# LNA.net
KiCad netlist of a schematic drawn in Altium Designer
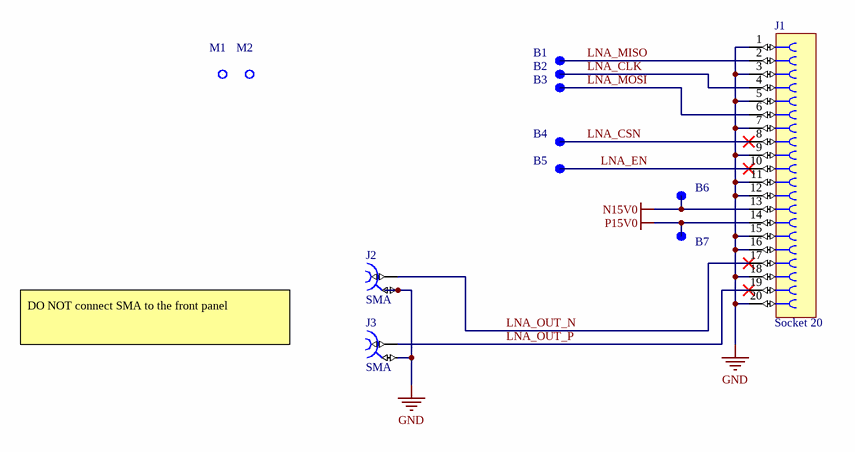
[diagram p0: LNA.SchDoc]

(export (version "E")
  (design (tool "Eeschema 10.0.6"))
  (components
    (comp (ref "B1")
      (value "SMD Pad")
      (footprint "C100")
      (description "Pad")
      (fields (field (name "PART NUMBER") "SMD_PAD_D1MM") (field (name "AUTHOR") "CERN DEM JLC"))
      (libsource (lib "Eletro-mechanical") (part "Single SMD Pad (Round)"))
    )
    (comp (ref "B2")
      (value "SMD Pad")
      (footprint "C100")
      (description "Pad")
      (fields (field (name "PART NUMBER") "SMD_PAD_D1MM") (field (name "AUTHOR") "CERN DEM JLC"))
      (libsource (lib "Eletro-mechanical") (part "Single SMD Pad (Round)"))
    )
    (comp (ref "B3")
      (value "SMD Pad")
      (footprint "C100")
      (description "Pad")
      (fields (field (name "PART NUMBER") "SMD_PAD_D1MM") (field (name "AUTHOR") "CERN DEM JLC"))
      (libsource (lib "Eletro-mechanical") (part "Single SMD Pad (Round)"))
    )
    (comp (ref "B4")
      (value "SMD Pad")
      (footprint "C100")
      (description "Pad")
      (fields (field (name "PART NUMBER") "SMD_PAD_D1MM") (field (name "AUTHOR") "CERN DEM JLC"))
      (libsource (lib "Eletro-mechanical") (part "Single SMD Pad (Round)"))
    )
    (comp (ref "B5")
      (value "SMD Pad")
      (footprint "C100")
      (description "Pad")
      (fields (field (name "PART NUMBER") "SMD_PAD_D1MM") (field (name "AUTHOR") "CERN DEM JLC"))
      (libsource (lib "Eletro-mechanical") (part "Single SMD Pad (Round)"))
    )
    (comp (ref "B6")
      (value "SMD Pad")
      (footprint "C100")
      (description "Pad")
      (fields (field (name "PART NUMBER") "SMD_PAD_D1MM") (field (name "AUTHOR") "CERN DEM JLC"))
      (libsource (lib "Eletro-mechanical") (part "Single SMD Pad (Round)"))
    )
    (comp (ref "B7")
      (value "SMD Pad")
      (footprint "C100")
      (description "Pad")
      (fields (field (name "PART NUMBER") "SMD_PAD_D1MM") (field (name "AUTHOR") "CERN DEM JLC"))
      (libsource (lib "Eletro-mechanical") (part "Single SMD Pad (Round)"))
    )
    (comp (ref "J1")
      (value "Socket 20")
      (footprint "SAMTEC_SSW-110-01-G-D")
      (description "Connector 20 Female")
      (fields
        (field (name "PART NUMBER") "SAMTEC_SSW-110-01-G-D")
        (field (name "MANUFACTURER") "SAMTEC")
        (field (name "AUTHOR") "CERN DEM JLC")
      )
      (libsource (lib "Connectors") (part "Connector 20 Female"))
    )
    (comp (ref "J2")
      (value "SMA")
      (footprint "AMPHENOL_132203-12")
      (description "RF Connector SMA Right Angle PCB Jack Through Hole 50 Ohm Bulkhead")
      (fields
        (field (name "MANUFACTURER") "Amphenol Connex")
        (field (name "MANUFACTURER PART NUMBER") "132203-12")
      )
      (libsource (lib "mb") (part "132203-12"))
    )
    (comp (ref "J3")
      (value "SMA")
      (footprint "AMPHENOL_132203-12")
      (description "RF Connector SMA Right Angle PCB Jack Through Hole 50 Ohm Bulkhead")
      (fields
        (field (name "MANUFACTURER") "Amphenol Connex")
        (field (name "MANUFACTURER PART NUMBER") "132203-12")
      )
      (libsource (lib "mb") (part "132203-12"))
    )
    (comp (ref "M1")
      (value "Plated Hole")
      (footprint "MTG300_600")
      (description "Single Terminal Socket")
      (fields (field (name "PART NUMBER") "PLATED_HOLE3.0_PAD6.0") (field (name "AUTHOR") "CERN DEM JLC"))
      (libsource (lib "Eletro-mechanical") (part "Single Terminal Socket"))
    )
    (comp (ref "M2")
      (value "Plated Hole")
      (footprint "MTG300_600")
      (description "Single Terminal Socket")
      (fields (field (name "PART NUMBER") "PLATED_HOLE3.0_PAD6.0") (field (name "AUTHOR") "CERN DEM JLC"))
      (libsource (lib "Eletro-mechanical") (part "Single Terminal Socket"))
    )
  )
  (nets
    (net (code "1") (name "/LNA_CLK") (class "Default")
      (node (ref "B2") (pin "1") (pinfunction "1_1") (pintype "bidirectional"))
      (node (ref "J1") (pin "4") (pinfunction "4_4") (pintype "bidirectional"))
    )
    (net (code "2") (name "/LNA_CSN") (class "Default")
      (node (ref "B4") (pin "1") (pinfunction "1_1") (pintype "bidirectional"))
      (node (ref "J1") (pin "8") (pinfunction "8_8") (pintype "bidirectional"))
    )
    (net (code "3") (name "/LNA_EN") (class "Default")
      (node (ref "B5") (pin "1") (pinfunction "1_1") (pintype "bidirectional"))
      (node (ref "J1") (pin "10") (pinfunction "10_10") (pintype "bidirectional"))
    )
    (net (code "4") (name "/LNA_MISO") (class "Default")
      (node (ref "B1") (pin "1") (pinfunction "1_1") (pintype "bidirectional"))
      (node (ref "J1") (pin "2") (pinfunction "2_2") (pintype "bidirectional"))
    )
    (net (code "5") (name "/LNA_MOSI") (class "Default")
      (node (ref "B3") (pin "1") (pinfunction "1_1") (pintype "bidirectional"))
      (node (ref "J1") (pin "6") (pinfunction "6_6") (pintype "bidirectional"))
    )
    (net (code "6") (name "/LNA_OUT_N") (class "Default")
      (node (ref "J1") (pin "17") (pinfunction "17_17") (pintype "bidirectional"))
      (node (ref "J2") (pin "1") (pinfunction "1_1") (pintype "bidirectional"))
    )
    (net (code "7") (name "/LNA_OUT_P") (class "Default")
      (node (ref "J1") (pin "19") (pinfunction "19_19") (pintype "bidirectional"))
      (node (ref "J3") (pin "1") (pinfunction "1_1") (pintype "bidirectional"))
    )
    (net (code "8") (name "GND") (class "Default")
      (node (ref "J1") (pin "1") (pinfunction "1_1") (pintype "bidirectional"))
      (node (ref "J1") (pin "11") (pinfunction "11_11") (pintype "bidirectional"))
      (node (ref "J1") (pin "12") (pinfunction "12_12") (pintype "bidirectional"))
      (node (ref "J1") (pin "15") (pinfunction "15_15") (pintype "bidirectional"))
      (node (ref "J1") (pin "16") (pinfunction "16_16") (pintype "bidirectional"))
      (node (ref "J1") (pin "18") (pinfunction "18_18") (pintype "bidirectional"))
      (node (ref "J1") (pin "20") (pinfunction "20_20") (pintype "bidirectional"))
      (node (ref "J1") (pin "3") (pinfunction "3_3") (pintype "bidirectional"))
      (node (ref "J1") (pin "5") (pinfunction "5_5") (pintype "bidirectional"))
      (node (ref "J1") (pin "7") (pinfunction "7_7") (pintype "bidirectional"))
      (node (ref "J1") (pin "9") (pinfunction "9_9") (pintype "bidirectional"))
      (node (ref "J2") (pin "2") (pinfunction "2_2") (pintype "bidirectional"))
      (node (ref "J3") (pin "2") (pinfunction "2_2") (pintype "bidirectional"))
    )
    (net (code "9") (name "N15V0") (class "Default")
      (node (ref "B6") (pin "1") (pinfunction "1_1") (pintype "bidirectional"))
      (node (ref "J1") (pin "13") (pinfunction "13_13") (pintype "bidirectional"))
    )
    (net (code "10") (name "P15V0") (class "Default")
      (node (ref "B7") (pin "1") (pinfunction "1_1") (pintype "bidirectional"))
      (node (ref "J1") (pin "14") (pinfunction "14_14") (pintype "bidirectional"))
    )
    (net (code "11") (name "unconnected-(M1-Pad1)") (class "Default")
      (node (ref "M1") (pin "1") (pinfunction "1_1") (pintype "bidirectional"))
    )
    (net (code "12") (name "unconnected-(M2-Pad1)") (class "Default")
      (node (ref "M2") (pin "1") (pinfunction "1_1") (pintype "bidirectional"))
    )
  )
)
